# CHIDIYA_UD_TALKING_V8.net
KiCad netlist of a schematic drawn in EAGLE
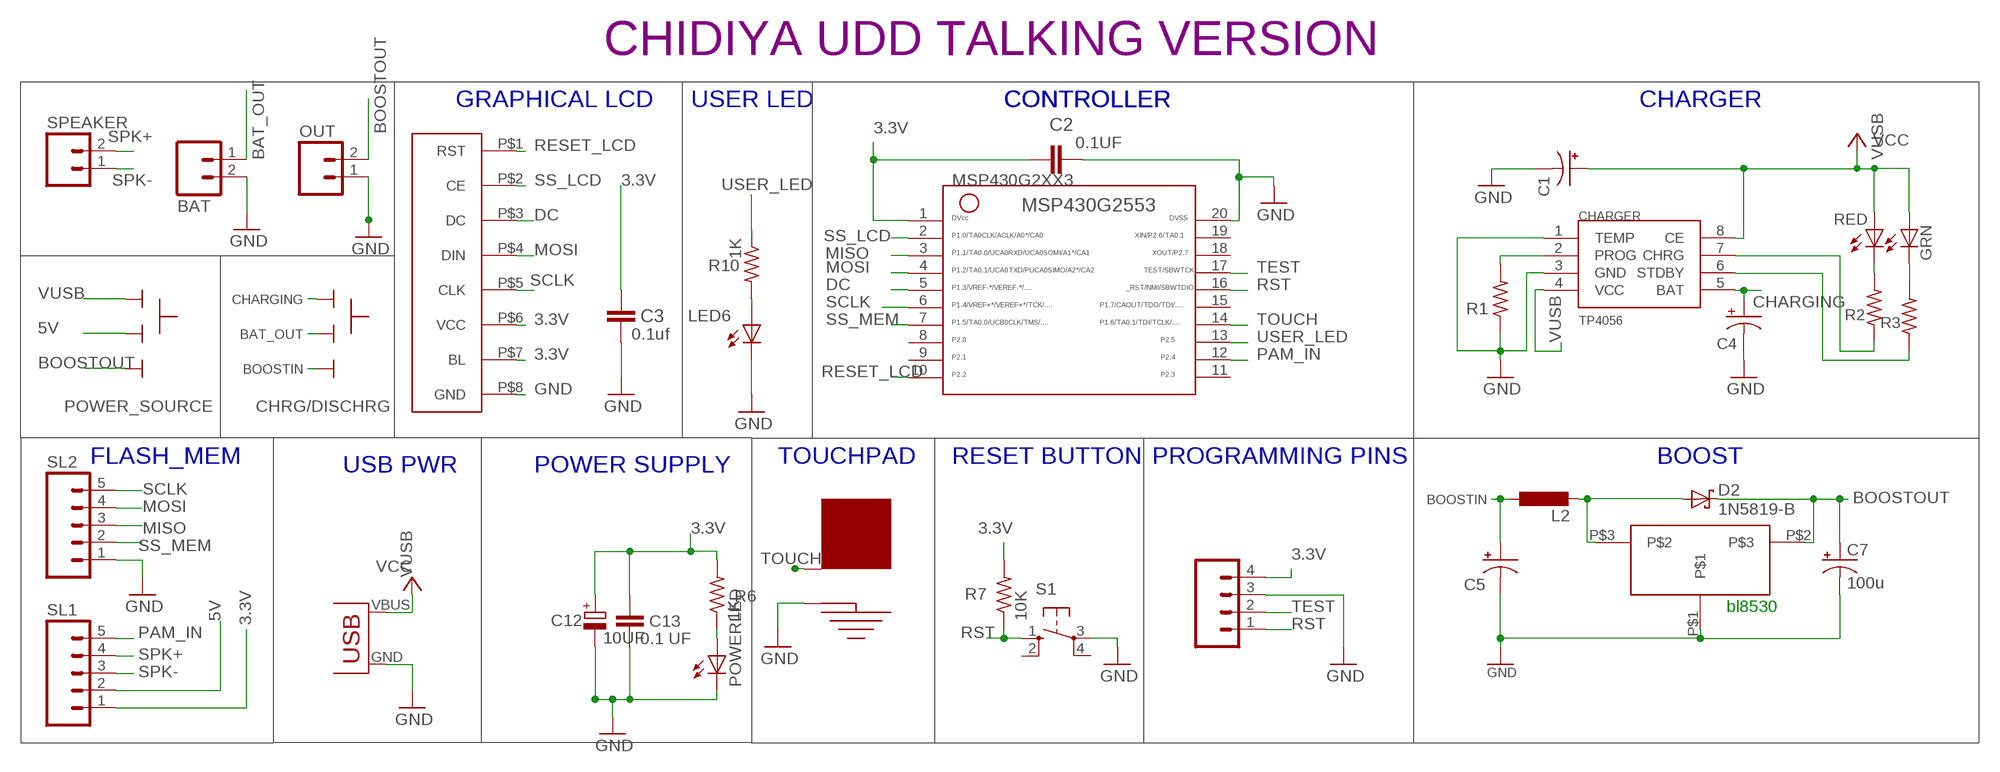
[diagram p0: schematic, sheet 1]

(export (version "E")
  (design (tool "Eeschema 10.0.6"))
  (components
    (comp (ref "BAT")
      (value "M02")
      (footprint "eagle-import:02P")
      (libsource (lib "eagle-import") (part "M02"))
    )
    (comp (ref "BOOST")
      (value "BL8530_5V")
      (footprint "eagle-import:BL8530_5V")
      (libsource (lib "eagle-import") (part "BL8530_5V"))
    )
    (comp (ref "C1")
      (value "10u")
      (footprint "eagle-import:C_6032-28R")
      (libsource (lib "eagle-import") (part "CEDT_JANUARY_2015_v7_CAP_POL_10V"))
    )
    (comp (ref "C2")
      (value "0.1UF")
      (footprint "eagle-import:C050-025X075")
      (libsource (lib "eagle-import") (part "CPO_C-EU050-025X075"))
    )
    (comp (ref "C3")
      (value "0.1uf")
      (footprint "eagle-import:C025-025X050")
      (libsource (lib "eagle-import") (part "C-EU025-025X050"))
    )
    (comp (ref "C4")
      (value "10u")
      (footprint "eagle-import:C_6032-28R")
      (libsource (lib "eagle-import") (part "CAP_POL_10V"))
    )
    (comp (ref "C5")
      (value "10u")
      (footprint "eagle-import:C_6032-28R")
      (libsource (lib "eagle-import") (part "CAP_POL_10V"))
    )
    (comp (ref "C7")
      (value "100u")
      (footprint "eagle-import:C_6032-28R")
      (libsource (lib "eagle-import") (part "CEDT_JANUARY_2015_v7_CAP_POL_10V"))
    )
    (comp (ref "C12")
      (value "10UF")
      (footprint "eagle-import:E2,5-5")
      (libsource (lib "eagle-import") (part "CPOL-EUE2.5-5"))
    )
    (comp (ref "C13")
      (value "0.1 UF")
      (footprint "eagle-import:C025-024X044")
      (libsource (lib "eagle-import") (part "CPO_C-EU025-024X044"))
    )
    (comp (ref "CHARGER")
      (value "TP4056")
      (footprint "eagle-import:SOP-8")
      (libsource (lib "eagle-import") (part "TP4056"))
    )
    (comp (ref "CHRG/DISCHRG")
      (value "SLIDESWITCH-BIG")
      (footprint "eagle-import:BIGSWITCH")
      (libsource (lib "eagle-import") (part "SLIDESWITCH-BIG"))
    )
    (comp (ref "D2")
      (value "1N5819-B")
      (footprint "eagle-import:DO41-7.6")
      (libsource (lib "eagle-import") (part "1N5819-B"))
    )
    (comp (ref "GRN")
      (value "LED3MM")
      (footprint "eagle-import:LED3MM")
      (libsource (lib "eagle-import") (part "LED3MM"))
    )
    (comp (ref "L2")
      (value "47uH")
      (footprint "eagle-import:L4532P")
      (libsource (lib "eagle-import") (part "L-EUL4532P"))
    )
    (comp (ref "LED6")
      (value "LED3MM")
      (footprint "eagle-import:LED3MM")
      (libsource (lib "eagle-import") (part "CEDT_JANUARY_2015_v5_LED3MM"))
    )
    (comp (ref "MSP430G2553")
      (value "MSP430G2553DIP20")
      (footprint "eagle-import:G2553-DIP20")
      (libsource (lib "eagle-import") (part "MSP430G2553DIP20"))
    )
    (comp (ref "OUT")
      (value "M02")
      (footprint "eagle-import:02P")
      (libsource (lib "eagle-import") (part "M02"))
    )
    (comp (ref "POWERLED")
      (value "LED3MM")
      (footprint "eagle-import:LED3MM")
      (libsource (lib "eagle-import") (part "CEDT_JANUARY_2015_v5_LED3MM"))
    )
    (comp (ref "POWER_SOURCE")
      (value "SLIDESWITCH-BIG")
      (footprint "eagle-import:BIGSWITCH")
      (libsource (lib "eagle-import") (part "SLIDESWITCH-BIG"))
    )
    (comp (ref "PROGRAM")
      (value "M04")
      (footprint "eagle-import:04P")
      (libsource (lib "eagle-import") (part "M04"))
    )
    (comp (ref "R1")
      (value "RESISTOR0805")
      (footprint "eagle-import:R0805")
      (libsource (lib "eagle-import") (part "RESISTOR0805"))
    )
    (comp (ref "R2")
      (value "470")
      (footprint "eagle-import:R0805")
      (libsource (lib "eagle-import") (part "RESISTOR0805"))
    )
    (comp (ref "R3")
      (value "470")
      (footprint "eagle-import:R0805")
      (libsource (lib "eagle-import") (part "RESISTOR0805"))
    )
    (comp (ref "R6")
      (value "1K")
      (footprint "eagle-import:0207_7")
      (libsource (lib "eagle-import") (part "R-US_0207/7"))
    )
    (comp (ref "R7")
      (value "10K")
      (footprint "eagle-import:0207_7")
      (libsource (lib "eagle-import") (part "R-US_0207/7"))
    )
    (comp (ref "R10")
      (value "1K")
      (footprint "eagle-import:0207_7")
      (libsource (lib "eagle-import") (part "R-US_0207/7"))
    )
    (comp (ref "RED")
      (value "LED3MM")
      (footprint "eagle-import:LED3MM")
      (libsource (lib "eagle-import") (part "LED3MM"))
    )
    (comp (ref "S1")
      (value "10-XX")
      (footprint "eagle-import:B3F-10XX")
      (fields (field (name "MPN") "B3F-1000"))
      (libsource (lib "eagle-import") (part "10-XX"))
    )
    (comp (ref "SL1")
      (value "M05")
      (footprint "eagle-import:05P")
      (libsource (lib "eagle-import") (part "M05"))
    )
    (comp (ref "SL2")
      (value "M05")
      (footprint "eagle-import:05P")
      (libsource (lib "eagle-import") (part "M05"))
    )
    (comp (ref "SPEAKER")
      (value "M02")
      (footprint "eagle-import:02P")
      (libsource (lib "eagle-import") (part "M02"))
    )
    (comp (ref "TOUCH1")
      (value "TOUCHPAD-20MM")
      (footprint "eagle-import:TOUCHPAD-20MM")
      (libsource (lib "eagle-import") (part "TOUCHPAD-20MM"))
    )
    (comp (ref "U$2")
      (value "USB(POWER)")
      (footprint "eagle-import:USB(POWER)")
      (libsource (lib "eagle-import") (part "USB(POWER)"))
    )
    (comp (ref "U$4")
      (value "NOKIA_5110_LCD")
      (footprint "eagle-import:NOKIA_5110_MODULE")
      (libsource (lib "eagle-import") (part "NOKIA_5110_LCD"))
    )
  )
  (nets
    (net (code "1") (name "/3.3V") (class "Default")
      (node (ref "C12") (pin "+") (pinfunction "+_+") (pintype "passive"))
      (node (ref "C13") (pin "1") (pinfunction "1_1") (pintype "passive"))
      (node (ref "C2") (pin "1") (pinfunction "1_1") (pintype "passive"))
      (node (ref "C3") (pin "1") (pinfunction "1_1") (pintype "passive"))
      (node (ref "MSP430G2553") (pin "1") (pinfunction "1_1") (pintype "power_in"))
      (node (ref "PROGRAM") (pin "4") (pinfunction "4_4") (pintype "passive"))
      (node (ref "R6") (pin "2") (pinfunction "2_2") (pintype "passive"))
      (node (ref "R7") (pin "2") (pinfunction "2_2") (pintype "passive"))
      (node (ref "SL1") (pin "1") (pinfunction "1_1") (pintype "passive"))
      (node (ref "U$4") (pin "P$6") (pinfunction "VCC_P$6") (pintype "bidirectional"))
      (node (ref "U$4") (pin "P$7") (pinfunction "BL_P$7") (pintype "bidirectional"))
    )
    (net (code "2") (name "/5V") (class "Default")
      (node (ref "POWER_SOURCE") (pin "2") (pinfunction "2_2") (pintype "bidirectional"))
      (node (ref "SL1") (pin "2") (pinfunction "2_2") (pintype "passive"))
    )
    (net (code "3") (name "/BAT_OUT") (class "Default")
      (node (ref "BAT") (pin "1") (pinfunction "1_1") (pintype "passive"))
      (node (ref "CHRG/DISCHRG") (pin "2") (pinfunction "2_2") (pintype "bidirectional"))
    )
    (net (code "4") (name "/BOOSTIN") (class "Default")
      (node (ref "C5") (pin "+") (pinfunction "+_+") (pintype "passive"))
      (node (ref "CHRG/DISCHRG") (pin "3") (pinfunction "3_3") (pintype "bidirectional"))
      (node (ref "L2") (pin "1") (pinfunction "1_1") (pintype "passive"))
    )
    (net (code "5") (name "/BOOSTOUT") (class "Default")
      (node (ref "BOOST") (pin "P$2") (pinfunction "P$3_P$2") (pintype "bidirectional"))
      (node (ref "C7") (pin "+") (pinfunction "+_+") (pintype "passive"))
      (node (ref "D2") (pin "C") (pinfunction "C_C") (pintype "passive"))
      (node (ref "OUT") (pin "2") (pinfunction "2_2") (pintype "passive"))
      (node (ref "POWER_SOURCE") (pin "3") (pinfunction "3_3") (pintype "bidirectional"))
    )
    (net (code "6") (name "/CHARGING") (class "Default")
      (node (ref "C4") (pin "+") (pinfunction "+_+") (pintype "passive"))
      (node (ref "CHARGER") (pin "5") (pinfunction "BAT_5") (pintype "bidirectional"))
      (node (ref "CHRG/DISCHRG") (pin "1") (pinfunction "1_1") (pintype "bidirectional"))
    )
    (net (code "7") (name "/DC") (class "Default")
      (node (ref "MSP430G2553") (pin "5") (pinfunction "5_5") (pintype "bidirectional"))
      (node (ref "U$4") (pin "P$3") (pinfunction "DC_P$3") (pintype "bidirectional"))
    )
    (net (code "8") (name "/MISO") (class "Default")
      (node (ref "MSP430G2553") (pin "3") (pinfunction "3_3") (pintype "bidirectional"))
      (node (ref "SL2") (pin "3") (pinfunction "3_3") (pintype "passive"))
    )
    (net (code "9") (name "/MOSI") (class "Default")
      (node (ref "MSP430G2553") (pin "4") (pinfunction "4_4") (pintype "bidirectional"))
      (node (ref "SL2") (pin "4") (pinfunction "4_4") (pintype "passive"))
      (node (ref "U$4") (pin "P$4") (pinfunction "DIN_P$4") (pintype "bidirectional"))
    )
    (net (code "10") (name "/PAM_IN") (class "Default")
      (node (ref "MSP430G2553") (pin "12") (pinfunction "12_12") (pintype "bidirectional"))
      (node (ref "SL1") (pin "5") (pinfunction "5_5") (pintype "passive"))
    )
    (net (code "11") (name "/RESET_LCD") (class "Default")
      (node (ref "MSP430G2553") (pin "10") (pinfunction "10_10") (pintype "bidirectional"))
      (node (ref "U$4") (pin "P$1") (pinfunction "RST_P$1") (pintype "bidirectional"))
    )
    (net (code "12") (name "/RST") (class "Default")
      (node (ref "MSP430G2553") (pin "16") (pinfunction "16_16") (pintype "bidirectional"))
      (node (ref "PROGRAM") (pin "1") (pinfunction "1_1") (pintype "passive"))
      (node (ref "R7") (pin "1") (pinfunction "1_1") (pintype "passive"))
      (node (ref "S1") (pin "1") (pinfunction "S_1") (pintype "passive"))
    )
    (net (code "13") (name "/SCLK") (class "Default")
      (node (ref "MSP430G2553") (pin "6") (pinfunction "6_6") (pintype "bidirectional"))
      (node (ref "SL2") (pin "5") (pinfunction "5_5") (pintype "passive"))
      (node (ref "U$4") (pin "P$5") (pinfunction "CLK_P$5") (pintype "bidirectional"))
    )
    (net (code "14") (name "/SPK+") (class "Default")
      (node (ref "SL1") (pin "4") (pinfunction "4_4") (pintype "passive"))
      (node (ref "SPEAKER") (pin "2") (pinfunction "2_2") (pintype "passive"))
    )
    (net (code "15") (name "/SPK-") (class "Default")
      (node (ref "SL1") (pin "3") (pinfunction "3_3") (pintype "passive"))
      (node (ref "SPEAKER") (pin "1") (pinfunction "1_1") (pintype "passive"))
    )
    (net (code "16") (name "/SS_LCD") (class "Default")
      (node (ref "MSP430G2553") (pin "2") (pinfunction "2_2") (pintype "bidirectional"))
      (node (ref "U$4") (pin "P$2") (pinfunction "CE_P$2") (pintype "bidirectional"))
    )
    (net (code "17") (name "/SS_MEM") (class "Default")
      (node (ref "MSP430G2553") (pin "7") (pinfunction "7_7") (pintype "bidirectional"))
      (node (ref "SL2") (pin "2") (pinfunction "2_2") (pintype "passive"))
    )
    (net (code "18") (name "/TEST") (class "Default")
      (node (ref "MSP430G2553") (pin "17") (pinfunction "17_17") (pintype "bidirectional"))
      (node (ref "PROGRAM") (pin "2") (pinfunction "2_2") (pintype "passive"))
    )
    (net (code "19") (name "/TOUCH") (class "Default")
      (node (ref "MSP430G2553") (pin "14") (pinfunction "14_14") (pintype "bidirectional"))
      (node (ref "TOUCH1") (pin "TOUCH") (pinfunction "TOUCH_TOUCH") (pintype "passive"))
    )
    (net (code "20") (name "/USER_LED") (class "Default")
      (node (ref "MSP430G2553") (pin "13") (pinfunction "13_13") (pintype "bidirectional"))
      (node (ref "R10") (pin "1") (pinfunction "1_1") (pintype "passive"))
    )
    (net (code "21") (name "GND") (class "Default")
      (node (ref "BAT") (pin "2") (pinfunction "2_2") (pintype "passive"))
      (node (ref "BOOST") (pin "P$1") (pinfunction "P$1_P$1") (pintype "bidirectional"))
      (node (ref "C1") (pin "-") (pinfunction "-_-") (pintype "passive"))
      (node (ref "C12") (pin "-") (pinfunction "-_-") (pintype "passive"))
      (node (ref "C13") (pin "2") (pinfunction "2_2") (pintype "passive"))
      (node (ref "C2") (pin "2") (pinfunction "2_2") (pintype "passive"))
      (node (ref "C3") (pin "2") (pinfunction "2_2") (pintype "passive"))
      (node (ref "C4") (pin "-") (pinfunction "-_-") (pintype "passive"))
      (node (ref "C5") (pin "-") (pinfunction "-_-") (pintype "passive"))
      (node (ref "C7") (pin "-") (pinfunction "-_-") (pintype "passive"))
      (node (ref "CHARGER") (pin "1") (pinfunction "TEMP_1") (pintype "bidirectional"))
      (node (ref "CHARGER") (pin "3") (pinfunction "GND_3") (pintype "bidirectional"))
      (node (ref "LED6") (pin "K") (pinfunction "C_K") (pintype "passive"))
      (node (ref "MSP430G2553") (pin "20") (pinfunction "20_20") (pintype "power_in"))
      (node (ref "OUT") (pin "1") (pinfunction "1_1") (pintype "passive"))
      (node (ref "POWERLED") (pin "K") (pinfunction "C_K") (pintype "passive"))
      (node (ref "PROGRAM") (pin "3") (pinfunction "3_3") (pintype "passive"))
      (node (ref "R1") (pin "1") (pinfunction "1_1") (pintype "passive"))
      (node (ref "S1") (pin "3") (pinfunction "P_3") (pintype "passive"))
      (node (ref "SL2") (pin "1") (pinfunction "1_1") (pintype "passive"))
      (node (ref "TOUCH1") (pin "GND") (pinfunction "GND_GND") (pintype "passive"))
      (node (ref "U$2") (pin "GND") (pinfunction "GND_GND") (pintype "power_in"))
      (node (ref "U$4") (pin "P$8") (pinfunction "GND_P$8") (pintype "bidirectional"))
    )
    (net (code "22") (name "Net-(BOOST-P$2)") (class "Default")
      (node (ref "BOOST") (pin "P$3") (pinfunction "P$2_P$3") (pintype "bidirectional"))
      (node (ref "D2") (pin "A") (pinfunction "A_A") (pintype "passive"))
      (node (ref "L2") (pin "2") (pinfunction "2_2") (pintype "passive"))
    )
    (net (code "23") (name "Net-(CHARGER-CHRG)") (class "Default")
      (node (ref "CHARGER") (pin "7") (pinfunction "CHRG_7") (pintype "bidirectional"))
      (node (ref "R2") (pin "1") (pinfunction "1_1") (pintype "passive"))
    )
    (net (code "24") (name "Net-(CHARGER-PROG)") (class "Default")
      (node (ref "CHARGER") (pin "2") (pinfunction "PROG_2") (pintype "bidirectional"))
      (node (ref "R1") (pin "2") (pinfunction "2_2") (pintype "passive"))
    )
    (net (code "25") (name "Net-(CHARGER-STDBY)") (class "Default")
      (node (ref "CHARGER") (pin "6") (pinfunction "STDBY_6") (pintype "bidirectional"))
      (node (ref "R3") (pin "1") (pinfunction "1_1") (pintype "passive"))
    )
    (net (code "26") (name "Net-(GRN-C)") (class "Default")
      (node (ref "GRN") (pin "K") (pinfunction "C_K") (pintype "passive"))
      (node (ref "R3") (pin "2") (pinfunction "2_2") (pintype "passive"))
    )
    (net (code "27") (name "Net-(LED6-PadA)") (class "Default")
      (node (ref "LED6") (pin "A") (pinfunction "A_A") (pintype "passive"))
      (node (ref "R10") (pin "2") (pinfunction "2_2") (pintype "passive"))
    )
    (net (code "28") (name "Net-(POWERLED-PadA)") (class "Default")
      (node (ref "POWERLED") (pin "A") (pinfunction "A_A") (pintype "passive"))
      (node (ref "R6") (pin "1") (pinfunction "1_1") (pintype "passive"))
    )
    (net (code "29") (name "Net-(RED-C)") (class "Default")
      (node (ref "R2") (pin "2") (pinfunction "2_2") (pintype "passive"))
      (node (ref "RED") (pin "K") (pinfunction "C_K") (pintype "passive"))
    )
    (net (code "30") (name "VCC") (class "Default")
      (node (ref "C1") (pin "+") (pinfunction "+_+") (pintype "passive"))
      (node (ref "CHARGER") (pin "4") (pinfunction "VCC_4") (pintype "bidirectional"))
      (node (ref "CHARGER") (pin "8") (pinfunction "CE_8") (pintype "bidirectional"))
      (node (ref "GRN") (pin "A") (pinfunction "A_A") (pintype "passive"))
      (node (ref "POWER_SOURCE") (pin "1") (pinfunction "1_1") (pintype "bidirectional"))
      (node (ref "RED") (pin "A") (pinfunction "A_A") (pintype "passive"))
      (node (ref "U$2") (pin "VBUS") (pinfunction "VCC_VBUS") (pintype "power_in"))
    )
    (net (code "31") (name "unconnected-(MSP430G2553-Pad8)") (class "Default")
      (node (ref "MSP430G2553") (pin "8") (pinfunction "8_8") (pintype "bidirectional"))
    )
    (net (code "32") (name "unconnected-(MSP430G2553-Pad9)") (class "Default")
      (node (ref "MSP430G2553") (pin "9") (pinfunction "9_9") (pintype "bidirectional"))
    )
    (net (code "33") (name "unconnected-(MSP430G2553-Pad11)") (class "Default")
      (node (ref "MSP430G2553") (pin "11") (pinfunction "11_11") (pintype "bidirectional"))
    )
    (net (code "34") (name "unconnected-(MSP430G2553-Pad15)") (class "Default")
      (node (ref "MSP430G2553") (pin "15") (pinfunction "15_15") (pintype "bidirectional"))
    )
    (net (code "35") (name "unconnected-(MSP430G2553-Pad18)") (class "Default")
      (node (ref "MSP430G2553") (pin "18") (pinfunction "18_18") (pintype "bidirectional"))
    )
    (net (code "36") (name "unconnected-(MSP430G2553-Pad19)") (class "Default")
      (node (ref "MSP430G2553") (pin "19") (pinfunction "19_19") (pintype "bidirectional"))
    )
    (net (code "37") (name "unconnected-(S1-P1-Pad4)") (class "Default")
      (node (ref "S1") (pin "4") (pinfunction "P1_4") (pintype "passive"))
    )
    (net (code "38") (name "unconnected-(S1-S1-Pad2)") (class "Default")
      (node (ref "S1") (pin "2") (pinfunction "S1_2") (pintype "passive"))
    )
  )
)
